# CAN_controller_rear_lighting.net
KiCad netlist of a schematic drawn in EAGLE
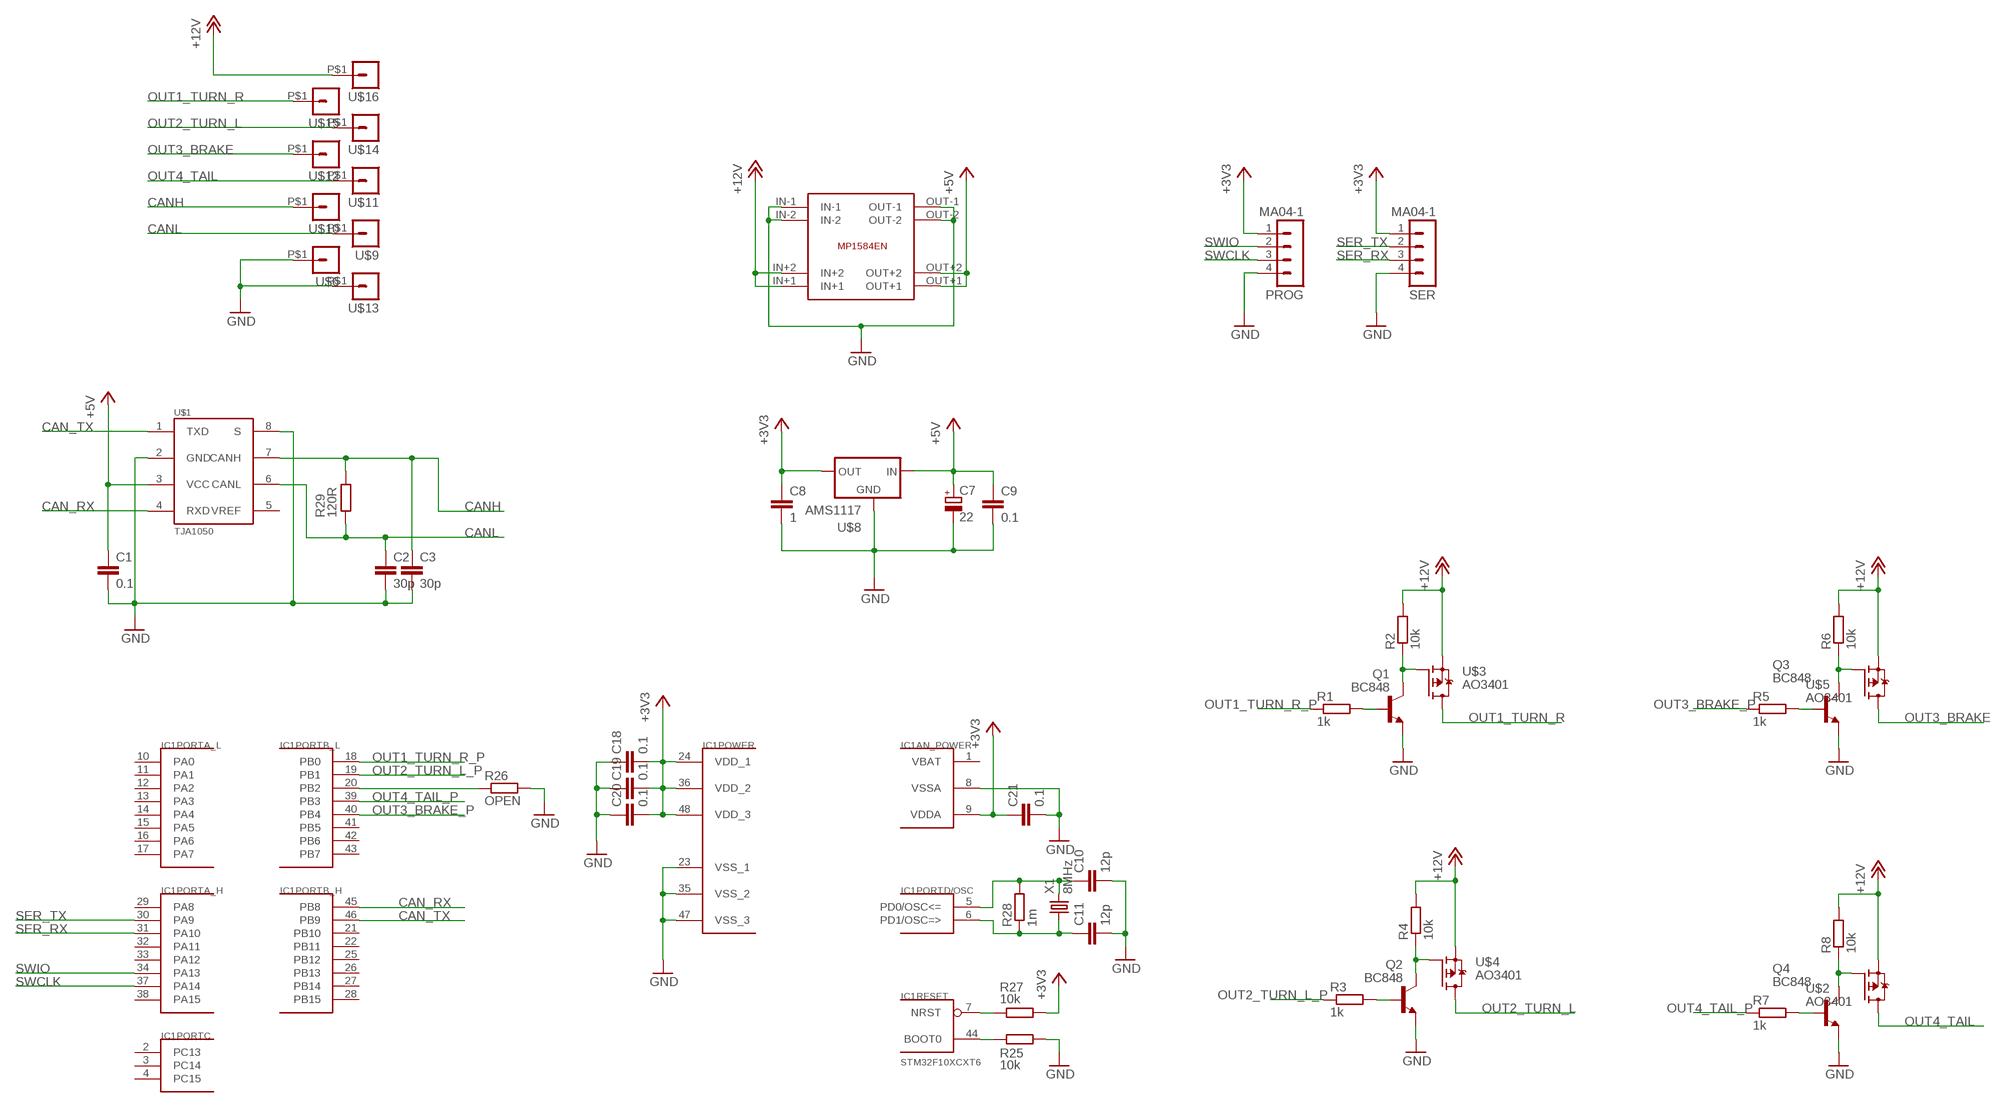
[diagram p0: schematic, sheet 1]

(export (version "E")
  (design (tool "Eeschema 10.0.6"))
  (components
    (comp (ref "C1")
      (value "0.1")
      (footprint "eagle-import:C0603")
      (libsource (lib "eagle-import") (part "C-EUC0603"))
    )
    (comp (ref "C2")
      (value "30p")
      (footprint "eagle-import:C0603")
      (libsource (lib "eagle-import") (part "C-EUC0603"))
    )
    (comp (ref "C3")
      (value "30p")
      (footprint "eagle-import:C0603")
      (libsource (lib "eagle-import") (part "C-EUC0603"))
    )
    (comp (ref "C7")
      (value "22")
      (footprint "eagle-import:A_3216-18R")
      (libsource (lib "eagle-import") (part "CPOL-EUA/3216-18R"))
    )
    (comp (ref "C8")
      (value "1")
      (footprint "eagle-import:C0805")
      (libsource (lib "eagle-import") (part "C-EUC0805"))
    )
    (comp (ref "C9")
      (value "0.1")
      (footprint "eagle-import:C0603")
      (libsource (lib "eagle-import") (part "C-EUC0603"))
    )
    (comp (ref "C10")
      (value "12p")
      (footprint "eagle-import:C0603")
      (libsource (lib "eagle-import") (part "C-EUC0603"))
    )
    (comp (ref "C11")
      (value "12p")
      (footprint "eagle-import:C0603")
      (libsource (lib "eagle-import") (part "C-EUC0603"))
    )
    (comp (ref "C18")
      (value "0.1")
      (footprint "eagle-import:C0603")
      (libsource (lib "eagle-import") (part "C-EUC0603"))
    )
    (comp (ref "C19")
      (value "0.1")
      (footprint "eagle-import:C0603")
      (libsource (lib "eagle-import") (part "C-EUC0603"))
    )
    (comp (ref "C20")
      (value "0.1")
      (footprint "eagle-import:C0603")
      (libsource (lib "eagle-import") (part "C-EUC0603"))
    )
    (comp (ref "C21")
      (value "0.1")
      (footprint "eagle-import:C0603")
      (libsource (lib "eagle-import") (part "C-EUC0603"))
    )
    (comp (ref "IC1")
      (value "STM32F10XCXT6")
      (footprint "eagle-import:TQFP48")
      (libsource (lib "eagle-import") (part "STM32F10XCXT6"))
    )
    (comp (ref "PROG")
      (value "MA04-1")
      (footprint "eagle-import:1X04")
      (libsource (lib "eagle-import") (part "MA04-1"))
    )
    (comp (ref "Q1")
      (value "BC848")
      (footprint "eagle-import:SOT23")
      (libsource (lib "eagle-import") (part "BC848SMDALT1"))
    )
    (comp (ref "Q2")
      (value "BC848")
      (footprint "eagle-import:SOT23")
      (libsource (lib "eagle-import") (part "BC848SMDALT1"))
    )
    (comp (ref "Q3")
      (value "BC848")
      (footprint "eagle-import:SOT23")
      (libsource (lib "eagle-import") (part "BC848SMDALT1"))
    )
    (comp (ref "Q4")
      (value "BC848")
      (footprint "eagle-import:SOT23")
      (libsource (lib "eagle-import") (part "BC848SMDALT1"))
    )
    (comp (ref "R1")
      (value "1k")
      (footprint "eagle-import:R0603")
      (libsource (lib "eagle-import") (part "R-EU_R0603"))
    )
    (comp (ref "R2")
      (value "10k")
      (footprint "eagle-import:R0603")
      (libsource (lib "eagle-import") (part "R-EU_R0603"))
    )
    (comp (ref "R3")
      (value "1k")
      (footprint "eagle-import:R0603")
      (libsource (lib "eagle-import") (part "R-EU_R0603"))
    )
    (comp (ref "R4")
      (value "10k")
      (footprint "eagle-import:R0603")
      (libsource (lib "eagle-import") (part "R-EU_R0603"))
    )
    (comp (ref "R5")
      (value "1k")
      (footprint "eagle-import:R0603")
      (libsource (lib "eagle-import") (part "R-EU_R0603"))
    )
    (comp (ref "R6")
      (value "10k")
      (footprint "eagle-import:R0603")
      (libsource (lib "eagle-import") (part "R-EU_R0603"))
    )
    (comp (ref "R7")
      (value "1k")
      (footprint "eagle-import:R0603")
      (libsource (lib "eagle-import") (part "R-EU_R0603"))
    )
    (comp (ref "R8")
      (value "10k")
      (footprint "eagle-import:R0603")
      (libsource (lib "eagle-import") (part "R-EU_R0603"))
    )
    (comp (ref "R25")
      (value "10k")
      (footprint "eagle-import:R0603")
      (libsource (lib "eagle-import") (part "R-EU_R0603"))
    )
    (comp (ref "R26")
      (value "OPEN")
      (footprint "eagle-import:R0603")
      (libsource (lib "eagle-import") (part "R-EU_R0603"))
    )
    (comp (ref "R27")
      (value "10k")
      (footprint "eagle-import:R0603")
      (libsource (lib "eagle-import") (part "R-EU_R0603"))
    )
    (comp (ref "R28")
      (value "1m")
      (footprint "eagle-import:R0603")
      (libsource (lib "eagle-import") (part "R-EU_R0603"))
    )
    (comp (ref "R29")
      (value "120R")
      (footprint "eagle-import:R0603")
      (libsource (lib "eagle-import") (part "R-EU_R0603"))
    )
    (comp (ref "SER")
      (value "MA04-1")
      (footprint "eagle-import:1X04")
      (libsource (lib "eagle-import") (part "MA04-1"))
    )
    (comp (ref "U$1")
      (value "TJA1050")
      (footprint "eagle-import:SO08")
      (libsource (lib "eagle-import") (part "TJA1050"))
    )
    (comp (ref "U$2")
      (value "AO3401")
      (footprint "eagle-import:SOT23")
      (libsource (lib "eagle-import") (part "AO3401"))
    )
    (comp (ref "U$3")
      (value "AO3401")
      (footprint "eagle-import:SOT23")
      (libsource (lib "eagle-import") (part "AO3401"))
    )
    (comp (ref "U$4")
      (value "AO3401")
      (footprint "eagle-import:SOT23")
      (libsource (lib "eagle-import") (part "AO3401"))
    )
    (comp (ref "U$5")
      (value "AO3401")
      (footprint "eagle-import:SOT23")
      (libsource (lib "eagle-import") (part "AO3401"))
    )
    (comp (ref "U$6")
      (value "MA01-1WIRE_PAD_1.5MM")
      (footprint "eagle-import:WIRE_PAD_1.5MM")
      (libsource (lib "eagle-import") (part "MA01-1WIRE_PAD_1.5MM"))
    )
    (comp (ref "U$7")
      (value "MP1584_DC-DC_MODULEMINI_22X17")
      (footprint "eagle-import:MP1584_DC-DC_MODULE")
      (libsource (lib "eagle-import") (part "MP1584_DC-DC_MODULEMINI_22X17"))
    )
    (comp (ref "U$8")
      (value "AMS1117")
      (footprint "eagle-import:SOT223-W")
      (libsource (lib "eagle-import") (part "AMS1117"))
    )
    (comp (ref "U$9")
      (value "MA01-1WIRE_PAD_1.5MM")
      (footprint "eagle-import:WIRE_PAD_1.5MM")
      (libsource (lib "eagle-import") (part "MA01-1WIRE_PAD_1.5MM"))
    )
    (comp (ref "U$10")
      (value "MA01-1WIRE_PAD_1.5MM")
      (footprint "eagle-import:WIRE_PAD_1.5MM")
      (libsource (lib "eagle-import") (part "MA01-1WIRE_PAD_1.5MM"))
    )
    (comp (ref "U$11")
      (value "MA01-1WIRE_PAD_1.5MM")
      (footprint "eagle-import:WIRE_PAD_1.5MM")
      (libsource (lib "eagle-import") (part "MA01-1WIRE_PAD_1.5MM"))
    )
    (comp (ref "U$12")
      (value "MA01-1WIRE_PAD_1.5MM")
      (footprint "eagle-import:WIRE_PAD_1.5MM")
      (libsource (lib "eagle-import") (part "MA01-1WIRE_PAD_1.5MM"))
    )
    (comp (ref "U$13")
      (value "MA01-1WIRE_PAD_1.5MM")
      (footprint "eagle-import:WIRE_PAD_1.5MM")
      (libsource (lib "eagle-import") (part "MA01-1WIRE_PAD_1.5MM"))
    )
    (comp (ref "U$14")
      (value "MA01-1WIRE_PAD_1.5MM")
      (footprint "eagle-import:WIRE_PAD_1.5MM")
      (libsource (lib "eagle-import") (part "MA01-1WIRE_PAD_1.5MM"))
    )
    (comp (ref "U$15")
      (value "MA01-1WIRE_PAD_1.5MM")
      (footprint "eagle-import:WIRE_PAD_1.5MM")
      (libsource (lib "eagle-import") (part "MA01-1WIRE_PAD_1.5MM"))
    )
    (comp (ref "U$16")
      (value "MA01-1WIRE_PAD_1.5MM")
      (footprint "eagle-import:WIRE_PAD_1.5MM")
      (libsource (lib "eagle-import") (part "MA01-1WIRE_PAD_1.5MM"))
    )
    (comp (ref "X1")
      (value "8MHz")
      (footprint "eagle-import:XTAL-ECX-53")
      (libsource (lib "eagle-import") (part "CRYSTAL"))
    )
  )
  (nets
    (net (code "1") (name "+3V3") (class "Default")
      (node (ref "C18") (pin "2") (pinfunction "2_2") (pintype "passive"))
      (node (ref "C19") (pin "2") (pinfunction "2_2") (pintype "passive"))
      (node (ref "C20") (pin "2") (pinfunction "2_2") (pintype "passive"))
      (node (ref "C21") (pin "1") (pinfunction "1_1") (pintype "passive"))
      (node (ref "C8") (pin "1") (pinfunction "1_1") (pintype "passive"))
      (node (ref "IC1") (pin "24") (pinfunction "VDD_1_24") (pintype "power_in"))
      (node (ref "IC1") (pin "36") (pinfunction "VDD_2_36") (pintype "power_in"))
      (node (ref "IC1") (pin "48") (pinfunction "VDD_3_48") (pintype "power_in"))
      (node (ref "IC1") (pin "9") (pinfunction "VDDA_9") (pintype "power_in"))
      (node (ref "PROG") (pin "1") (pinfunction "1_1") (pintype "passive"))
      (node (ref "R27") (pin "2") (pinfunction "2_2") (pintype "passive"))
      (node (ref "SER") (pin "1") (pinfunction "1_1") (pintype "passive"))
      (node (ref "U$8") (pin "2") (pinfunction "OUT_2") (pintype "passive"))
    )
    (net (code "2") (name "+5V") (class "Default")
      (node (ref "C1") (pin "1") (pinfunction "1_1") (pintype "passive"))
      (node (ref "C7") (pin "+") (pinfunction "+_+") (pintype "passive"))
      (node (ref "C9") (pin "1") (pinfunction "1_1") (pintype "passive"))
      (node (ref "U$1") (pin "3") (pinfunction "VCC_3") (pintype "bidirectional"))
      (node (ref "U$7") (pin "OUT+1") (pinfunction "OUT+1_OUT+1") (pintype "bidirectional"))
      (node (ref "U$7") (pin "OUT+2") (pinfunction "OUT+2_OUT+2") (pintype "bidirectional"))
      (node (ref "U$8") (pin "3") (pinfunction "IN_3") (pintype "input"))
    )
    (net (code "3") (name "+12V") (class "Default")
      (node (ref "R2") (pin "2") (pinfunction "2_2") (pintype "passive"))
      (node (ref "R4") (pin "2") (pinfunction "2_2") (pintype "passive"))
      (node (ref "R6") (pin "2") (pinfunction "2_2") (pintype "passive"))
      (node (ref "R8") (pin "2") (pinfunction "2_2") (pintype "passive"))
      (node (ref "U$16") (pin "P$1") (pinfunction "1_P$1") (pintype "passive"))
      (node (ref "U$2") (pin "2") (pinfunction "S_2") (pintype "passive"))
      (node (ref "U$3") (pin "2") (pinfunction "S_2") (pintype "passive"))
      (node (ref "U$4") (pin "2") (pinfunction "S_2") (pintype "passive"))
      (node (ref "U$5") (pin "2") (pinfunction "S_2") (pintype "passive"))
      (node (ref "U$7") (pin "IN+1") (pinfunction "IN+1_IN+1") (pintype "bidirectional"))
      (node (ref "U$7") (pin "IN+2") (pinfunction "IN+2_IN+2") (pintype "bidirectional"))
    )
    (net (code "4") (name "/CANH") (class "Default")
      (node (ref "C3") (pin "1") (pinfunction "1_1") (pintype "passive"))
      (node (ref "R29") (pin "2") (pinfunction "2_2") (pintype "passive"))
      (node (ref "U$1") (pin "7") (pinfunction "CANH_7") (pintype "bidirectional"))
      (node (ref "U$10") (pin "P$1") (pinfunction "1_P$1") (pintype "passive"))
    )
    (net (code "5") (name "/CANL") (class "Default")
      (node (ref "C2") (pin "1") (pinfunction "1_1") (pintype "passive"))
      (node (ref "R29") (pin "1") (pinfunction "1_1") (pintype "passive"))
      (node (ref "U$1") (pin "6") (pinfunction "CANL_6") (pintype "bidirectional"))
      (node (ref "U$9") (pin "P$1") (pinfunction "1_P$1") (pintype "passive"))
    )
    (net (code "6") (name "/CAN_RX") (class "Default")
      (node (ref "IC1") (pin "45") (pinfunction "PB8_45") (pintype "bidirectional"))
      (node (ref "U$1") (pin "4") (pinfunction "RXD_4") (pintype "bidirectional"))
    )
    (net (code "7") (name "/CAN_TX") (class "Default")
      (node (ref "IC1") (pin "46") (pinfunction "PB9_46") (pintype "bidirectional"))
      (node (ref "U$1") (pin "1") (pinfunction "TXD_1") (pintype "bidirectional"))
    )
    (net (code "8") (name "/OUT1_TURN_R") (class "Default")
      (node (ref "U$15") (pin "P$1") (pinfunction "1_P$1") (pintype "passive"))
      (node (ref "U$3") (pin "3") (pinfunction "D_3") (pintype "passive"))
    )
    (net (code "9") (name "/OUT1_TURN_R_P") (class "Default")
      (node (ref "IC1") (pin "18") (pinfunction "PB0_18") (pintype "bidirectional"))
      (node (ref "R1") (pin "1") (pinfunction "1_1") (pintype "passive"))
    )
    (net (code "10") (name "/OUT2_TURN_L") (class "Default")
      (node (ref "U$14") (pin "P$1") (pinfunction "1_P$1") (pintype "passive"))
      (node (ref "U$4") (pin "3") (pinfunction "D_3") (pintype "passive"))
    )
    (net (code "11") (name "/OUT2_TURN_L_P") (class "Default")
      (node (ref "IC1") (pin "19") (pinfunction "PB1_19") (pintype "bidirectional"))
      (node (ref "R3") (pin "1") (pinfunction "1_1") (pintype "passive"))
    )
    (net (code "12") (name "/OUT3_BRAKE") (class "Default")
      (node (ref "U$12") (pin "P$1") (pinfunction "1_P$1") (pintype "passive"))
      (node (ref "U$5") (pin "3") (pinfunction "D_3") (pintype "passive"))
    )
    (net (code "13") (name "/OUT3_BRAKE_P") (class "Default")
      (node (ref "IC1") (pin "40") (pinfunction "PB4_40") (pintype "bidirectional"))
      (node (ref "R5") (pin "1") (pinfunction "1_1") (pintype "passive"))
    )
    (net (code "14") (name "/OUT4_TAIL") (class "Default")
      (node (ref "U$11") (pin "P$1") (pinfunction "1_P$1") (pintype "passive"))
      (node (ref "U$2") (pin "3") (pinfunction "D_3") (pintype "passive"))
    )
    (net (code "15") (name "/OUT4_TAIL_P") (class "Default")
      (node (ref "IC1") (pin "39") (pinfunction "PB3_39") (pintype "bidirectional"))
      (node (ref "R7") (pin "1") (pinfunction "1_1") (pintype "passive"))
    )
    (net (code "16") (name "/SER_RX") (class "Default")
      (node (ref "IC1") (pin "31") (pinfunction "PA10_31") (pintype "bidirectional"))
      (node (ref "SER") (pin "3") (pinfunction "3_3") (pintype "passive"))
    )
    (net (code "17") (name "/SER_TX") (class "Default")
      (node (ref "IC1") (pin "30") (pinfunction "PA9_30") (pintype "bidirectional"))
      (node (ref "SER") (pin "2") (pinfunction "2_2") (pintype "passive"))
    )
    (net (code "18") (name "/SWCLK") (class "Default")
      (node (ref "IC1") (pin "37") (pinfunction "PA14_37") (pintype "bidirectional"))
      (node (ref "PROG") (pin "3") (pinfunction "3_3") (pintype "passive"))
    )
    (net (code "19") (name "/SWIO") (class "Default")
      (node (ref "IC1") (pin "34") (pinfunction "PA13_34") (pintype "bidirectional"))
      (node (ref "PROG") (pin "2") (pinfunction "2_2") (pintype "passive"))
    )
    (net (code "20") (name "/VBAT") (class "Default")
      (node (ref "IC1") (pin "1") (pinfunction "VBAT_1") (pintype "power_in"))
    )
    (net (code "21") (name "GND") (class "Default")
      (node (ref "C1") (pin "2") (pinfunction "2_2") (pintype "passive"))
      (node (ref "C10") (pin "2") (pinfunction "2_2") (pintype "passive"))
      (node (ref "C11") (pin "2") (pinfunction "2_2") (pintype "passive"))
      (node (ref "C18") (pin "1") (pinfunction "1_1") (pintype "passive"))
      (node (ref "C19") (pin "1") (pinfunction "1_1") (pintype "passive"))
      (node (ref "C2") (pin "2") (pinfunction "2_2") (pintype "passive"))
      (node (ref "C20") (pin "1") (pinfunction "1_1") (pintype "passive"))
      (node (ref "C21") (pin "2") (pinfunction "2_2") (pintype "passive"))
      (node (ref "C3") (pin "2") (pinfunction "2_2") (pintype "passive"))
      (node (ref "C7") (pin "-") (pinfunction "-_-") (pintype "passive"))
      (node (ref "C8") (pin "2") (pinfunction "2_2") (pintype "passive"))
      (node (ref "C9") (pin "2") (pinfunction "2_2") (pintype "passive"))
      (node (ref "IC1") (pin "23") (pinfunction "VSS_1_23") (pintype "power_in"))
      (node (ref "IC1") (pin "35") (pinfunction "VSS_2_35") (pintype "power_in"))
      (node (ref "IC1") (pin "47") (pinfunction "VSS_3_47") (pintype "power_in"))
      (node (ref "IC1") (pin "8") (pinfunction "VSSA_8") (pintype "power_in"))
      (node (ref "PROG") (pin "4") (pinfunction "4_4") (pintype "passive"))
      (node (ref "Q1") (pin "2") (pinfunction "E_2") (pintype "passive"))
      (node (ref "Q2") (pin "2") (pinfunction "E_2") (pintype "passive"))
      (node (ref "Q3") (pin "2") (pinfunction "E_2") (pintype "passive"))
      (node (ref "Q4") (pin "2") (pinfunction "E_2") (pintype "passive"))
      (node (ref "R25") (pin "2") (pinfunction "2_2") (pintype "passive"))
      (node (ref "R26") (pin "2") (pinfunction "2_2") (pintype "passive"))
      (node (ref "SER") (pin "4") (pinfunction "4_4") (pintype "passive"))
      (node (ref "U$1") (pin "2") (pinfunction "GND_2") (pintype "bidirectional"))
      (node (ref "U$1") (pin "8") (pinfunction "S_8") (pintype "bidirectional"))
      (node (ref "U$13") (pin "P$1") (pinfunction "1_P$1") (pintype "passive"))
      (node (ref "U$6") (pin "P$1") (pinfunction "1_P$1") (pintype "passive"))
      (node (ref "U$7") (pin "IN-1") (pinfunction "IN-1_IN-1") (pintype "bidirectional"))
      (node (ref "U$7") (pin "IN-2") (pinfunction "IN-2_IN-2") (pintype "bidirectional"))
      (node (ref "U$7") (pin "OUT-1") (pinfunction "OUT-1_OUT-1") (pintype "bidirectional"))
      (node (ref "U$7") (pin "OUT-2") (pinfunction "OUT-2_OUT-2") (pintype "bidirectional"))
      (node (ref "U$8") (pin "1") (pinfunction "GND_1") (pintype "input"))
    )
    (net (code "22") (name "Net-(IC1E-PB2)") (class "Default")
      (node (ref "IC1") (pin "20") (pinfunction "PB2_20") (pintype "bidirectional"))
      (node (ref "R26") (pin "1") (pinfunction "1_1") (pintype "passive"))
    )
    (net (code "23") (name "Net-(IC1G-PD0{slash}OSC<=)") (class "Default")
      (node (ref "C10") (pin "1") (pinfunction "1_1") (pintype "passive"))
      (node (ref "IC1") (pin "5") (pinfunction "PD0/OSC<=_5") (pintype "bidirectional"))
      (node (ref "R28") (pin "2") (pinfunction "2_2") (pintype "passive"))
      (node (ref "X1") (pin "2") (pinfunction "2_2") (pintype "passive"))
    )
    (net (code "24") (name "Net-(IC1G-PD1{slash}OSC=>)") (class "Default")
      (node (ref "C11") (pin "1") (pinfunction "1_1") (pintype "passive"))
      (node (ref "IC1") (pin "6") (pinfunction "PD1/OSC=>_6") (pintype "bidirectional"))
      (node (ref "R28") (pin "1") (pinfunction "1_1") (pintype "passive"))
      (node (ref "X1") (pin "1") (pinfunction "1_1") (pintype "passive"))
    )
    (net (code "25") (name "Net-(IC1I-BOOT0)") (class "Default")
      (node (ref "IC1") (pin "44") (pinfunction "BOOT0_44") (pintype "input"))
      (node (ref "R25") (pin "1") (pinfunction "1_1") (pintype "passive"))
    )
    (net (code "26") (name "Net-(IC1I-NRST)") (class "Default")
      (node (ref "IC1") (pin "7") (pinfunction "NRST_7") (pintype "input"))
      (node (ref "R27") (pin "1") (pinfunction "1_1") (pintype "passive"))
    )
    (net (code "27") (name "Net-(Q1-B)") (class "Default")
      (node (ref "Q1") (pin "1") (pinfunction "B_1") (pintype "passive"))
      (node (ref "R1") (pin "2") (pinfunction "2_2") (pintype "passive"))
    )
    (net (code "28") (name "Net-(Q1-C)") (class "Default")
      (node (ref "Q1") (pin "3") (pinfunction "C_3") (pintype "passive"))
      (node (ref "R2") (pin "1") (pinfunction "1_1") (pintype "passive"))
      (node (ref "U$3") (pin "1") (pinfunction "G_1") (pintype "passive"))
    )
    (net (code "29") (name "Net-(Q2-B)") (class "Default")
      (node (ref "Q2") (pin "1") (pinfunction "B_1") (pintype "passive"))
      (node (ref "R3") (pin "2") (pinfunction "2_2") (pintype "passive"))
    )
    (net (code "30") (name "Net-(Q2-C)") (class "Default")
      (node (ref "Q2") (pin "3") (pinfunction "C_3") (pintype "passive"))
      (node (ref "R4") (pin "1") (pinfunction "1_1") (pintype "passive"))
      (node (ref "U$4") (pin "1") (pinfunction "G_1") (pintype "passive"))
    )
    (net (code "31") (name "Net-(Q3-B)") (class "Default")
      (node (ref "Q3") (pin "1") (pinfunction "B_1") (pintype "passive"))
      (node (ref "R5") (pin "2") (pinfunction "2_2") (pintype "passive"))
    )
    (net (code "32") (name "Net-(Q3-C)") (class "Default")
      (node (ref "Q3") (pin "3") (pinfunction "C_3") (pintype "passive"))
      (node (ref "R6") (pin "1") (pinfunction "1_1") (pintype "passive"))
      (node (ref "U$5") (pin "1") (pinfunction "G_1") (pintype "passive"))
    )
    (net (code "33") (name "Net-(Q4-B)") (class "Default")
      (node (ref "Q4") (pin "1") (pinfunction "B_1") (pintype "passive"))
      (node (ref "R7") (pin "2") (pinfunction "2_2") (pintype "passive"))
    )
    (net (code "34") (name "Net-(Q4-C)") (class "Default")
      (node (ref "Q4") (pin "3") (pinfunction "C_3") (pintype "passive"))
      (node (ref "R8") (pin "1") (pinfunction "1_1") (pintype "passive"))
      (node (ref "U$2") (pin "1") (pinfunction "G_1") (pintype "passive"))
    )
    (net (code "35") (name "unconnected-(IC1B-PA8-Pad29)") (class "Default")
      (node (ref "IC1") (pin "29") (pinfunction "PA8_29") (pintype "bidirectional"))
    )
    (net (code "36") (name "unconnected-(IC1B-PA11-Pad32)") (class "Default")
      (node (ref "IC1") (pin "32") (pinfunction "PA11_32") (pintype "bidirectional"))
    )
    (net (code "37") (name "unconnected-(IC1B-PA12-Pad33)") (class "Default")
      (node (ref "IC1") (pin "33") (pinfunction "PA12_33") (pintype "bidirectional"))
    )
    (net (code "38") (name "unconnected-(IC1B-PA15-Pad38)") (class "Default")
      (node (ref "IC1") (pin "38") (pinfunction "PA15_38") (pintype "bidirectional"))
    )
    (net (code "39") (name "unconnected-(IC1C-PA0-Pad10)") (class "Default")
      (node (ref "IC1") (pin "10") (pinfunction "PA0_10") (pintype "bidirectional"))
    )
    (net (code "40") (name "unconnected-(IC1C-PA1-Pad11)") (class "Default")
      (node (ref "IC1") (pin "11") (pinfunction "PA1_11") (pintype "bidirectional"))
    )
    (net (code "41") (name "unconnected-(IC1C-PA2-Pad12)") (class "Default")
      (node (ref "IC1") (pin "12") (pinfunction "PA2_12") (pintype "bidirectional"))
    )
    (net (code "42") (name "unconnected-(IC1C-PA3-Pad13)") (class "Default")
      (node (ref "IC1") (pin "13") (pinfunction "PA3_13") (pintype "bidirectional"))
    )
    (net (code "43") (name "unconnected-(IC1C-PA4-Pad14)") (class "Default")
      (node (ref "IC1") (pin "14") (pinfunction "PA4_14") (pintype "bidirectional"))
    )
    (net (code "44") (name "unconnected-(IC1C-PA5-Pad15)") (class "Default")
      (node (ref "IC1") (pin "15") (pinfunction "PA5_15") (pintype "bidirectional"))
    )
    (net (code "45") (name "unconnected-(IC1C-PA6-Pad16)") (class "Default")
      (node (ref "IC1") (pin "16") (pinfunction "PA6_16") (pintype "bidirectional"))
    )
    (net (code "46") (name "unconnected-(IC1C-PA7-Pad17)") (class "Default")
      (node (ref "IC1") (pin "17") (pinfunction "PA7_17") (pintype "bidirectional"))
    )
    (net (code "47") (name "unconnected-(IC1D-PB10-Pad21)") (class "Default")
      (node (ref "IC1") (pin "21") (pinfunction "PB10_21") (pintype "bidirectional"))
    )
    (net (code "48") (name "unconnected-(IC1D-PB11-Pad22)") (class "Default")
      (node (ref "IC1") (pin "22") (pinfunction "PB11_22") (pintype "bidirectional"))
    )
    (net (code "49") (name "unconnected-(IC1D-PB12-Pad25)") (class "Default")
      (node (ref "IC1") (pin "25") (pinfunction "PB12_25") (pintype "bidirectional"))
    )
    (net (code "50") (name "unconnected-(IC1D-PB13-Pad26)") (class "Default")
      (node (ref "IC1") (pin "26") (pinfunction "PB13_26") (pintype "bidirectional"))
    )
    (net (code "51") (name "unconnected-(IC1D-PB14-Pad27)") (class "Default")
      (node (ref "IC1") (pin "27") (pinfunction "PB14_27") (pintype "bidirectional"))
    )
    (net (code "52") (name "unconnected-(IC1D-PB15-Pad28)") (class "Default")
      (node (ref "IC1") (pin "28") (pinfunction "PB15_28") (pintype "bidirectional"))
    )
    (net (code "53") (name "unconnected-(IC1E-PB5-Pad41)") (class "Default")
      (node (ref "IC1") (pin "41") (pinfunction "PB5_41") (pintype "bidirectional"))
    )
    (net (code "54") (name "unconnected-(IC1E-PB6-Pad42)") (class "Default")
      (node (ref "IC1") (pin "42") (pinfunction "PB6_42") (pintype "bidirectional"))
    )
    (net (code "55") (name "unconnected-(IC1E-PB7-Pad43)") (class "Default")
      (node (ref "IC1") (pin "43") (pinfunction "PB7_43") (pintype "bidirectional"))
    )
    (net (code "56") (name "unconnected-(IC1F-PC13-Pad2)") (class "Default")
      (node (ref "IC1") (pin "2") (pinfunction "PC13_2") (pintype "bidirectional"))
    )
    (net (code "57") (name "unconnected-(IC1F-PC14-Pad3)") (class "Default")
      (node (ref "IC1") (pin "3") (pinfunction "PC14_3") (pintype "bidirectional"))
    )
    (net (code "58") (name "unconnected-(IC1F-PC15-Pad4)") (class "Default")
      (node (ref "IC1") (pin "4") (pinfunction "PC15_4") (pintype "bidirectional"))
    )
    (net (code "59") (name "unconnected-(U$1-VREF-Pad5)") (class "Default")
      (node (ref "U$1") (pin "5") (pinfunction "VREF_5") (pintype "bidirectional"))
    )
  )
)
